# USB.net
KiCad netlist of a schematic drawn in Altium Designer
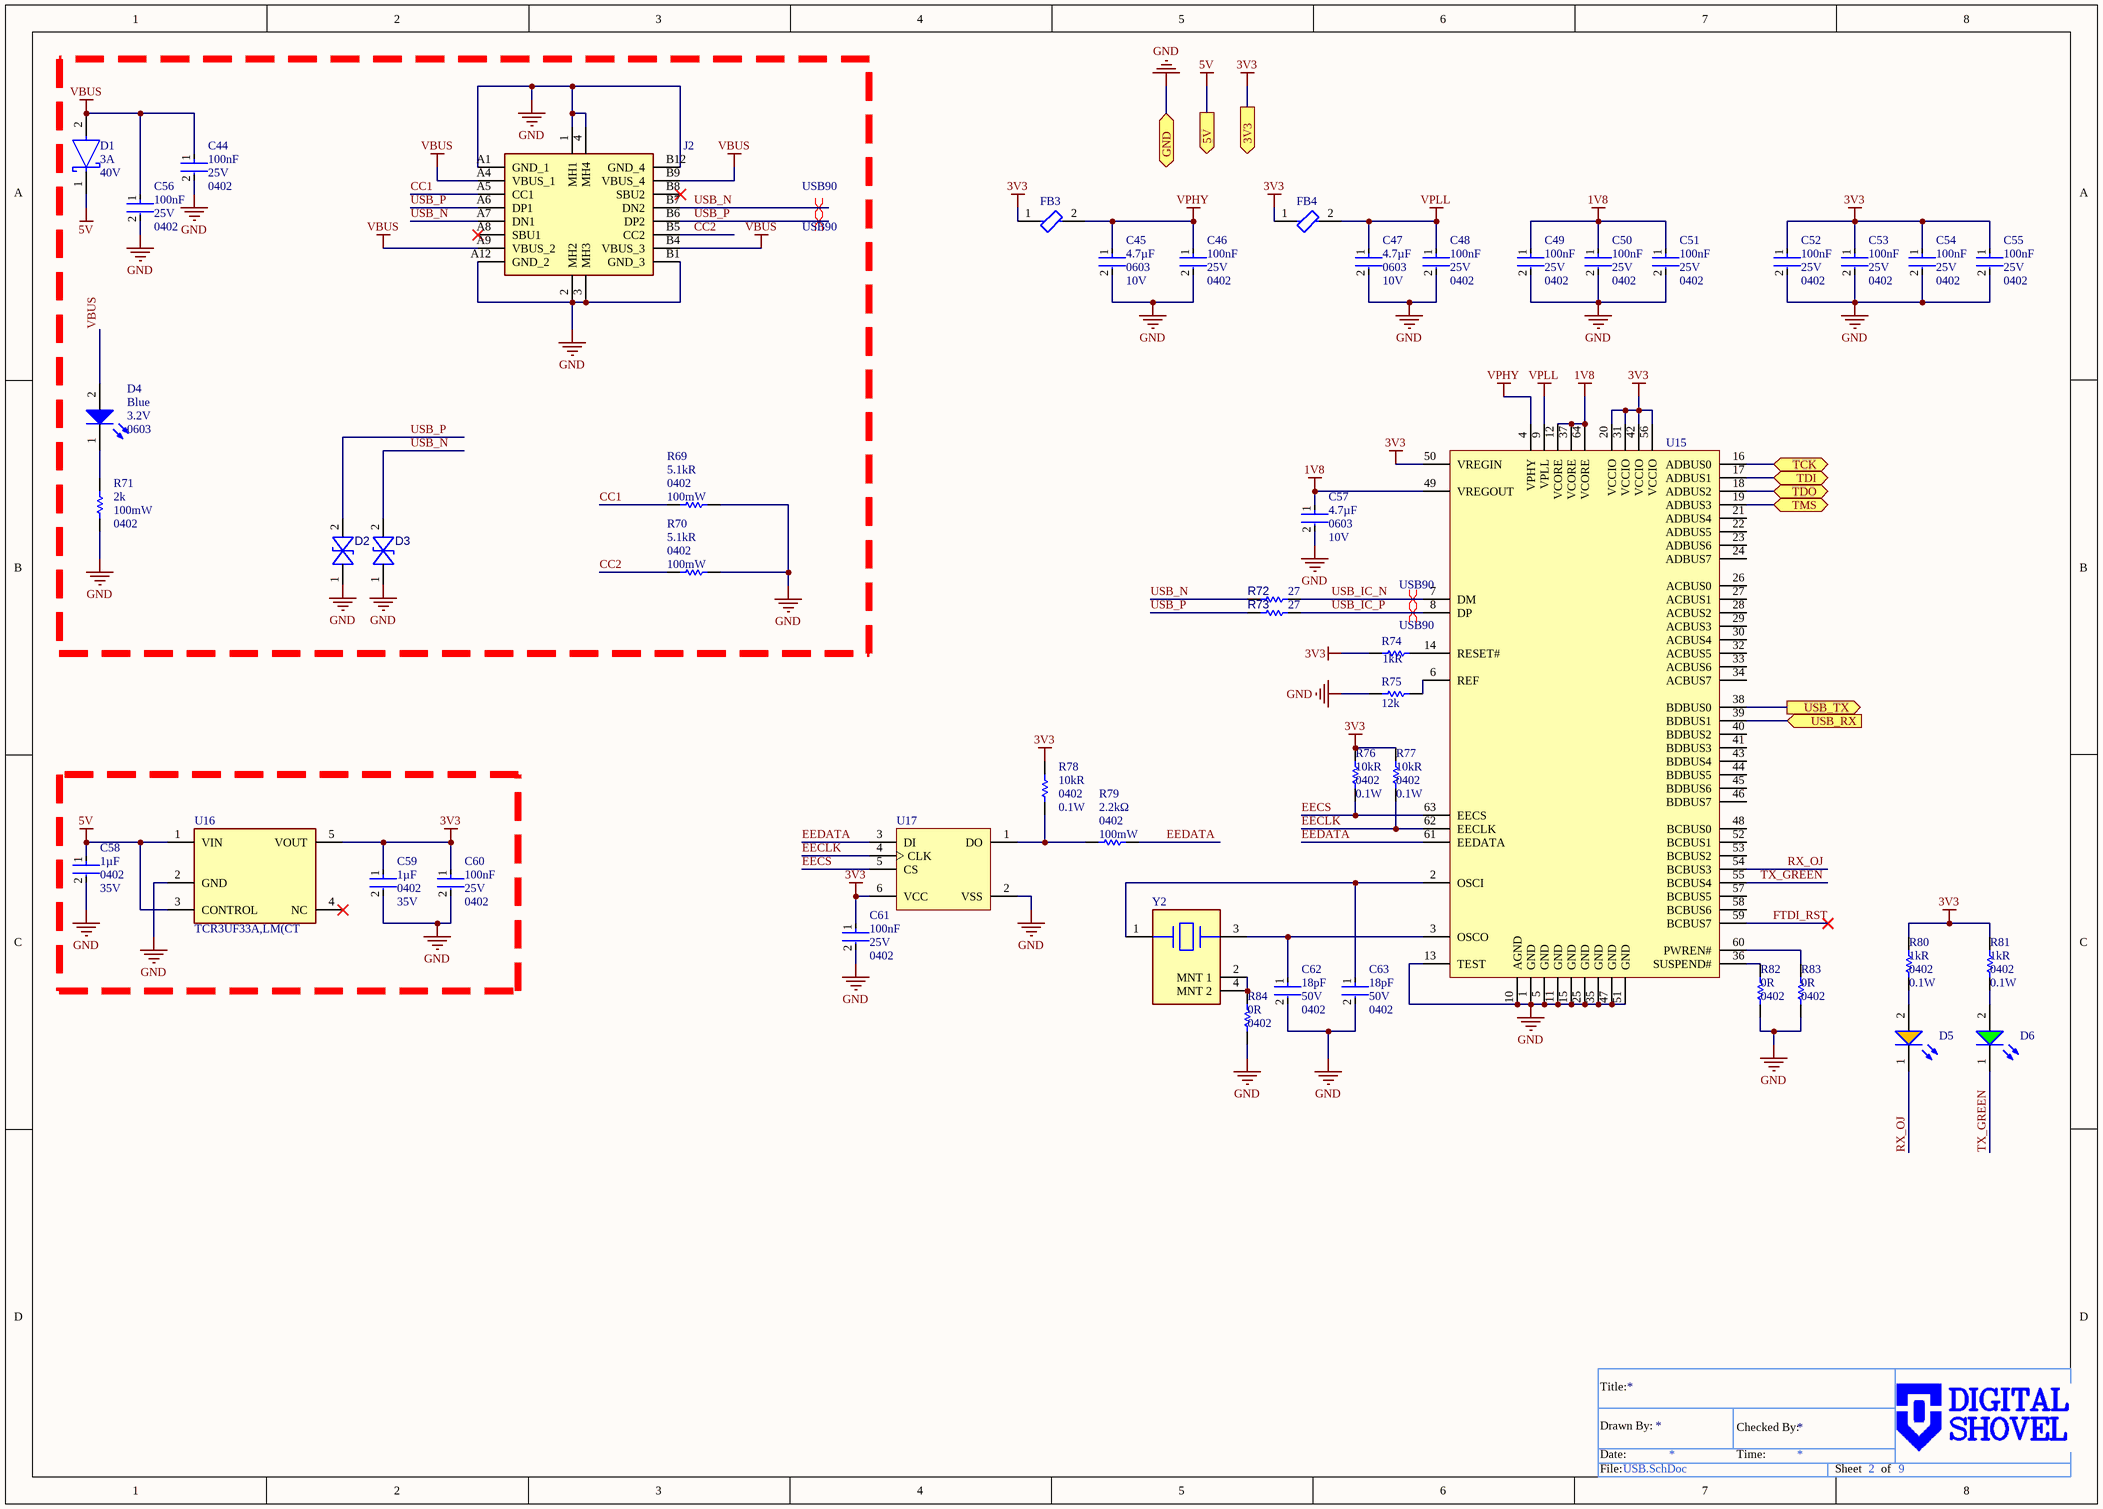
[diagram p0: USB.SchDoc]

(export (version "E")
  (design (tool "Eeschema 10.0.6"))
  (components
    (comp (ref "C44")
      (value "100nF")
      (footprint "FP-CL830-IPC_A")
      (fields
        (field (name "VOLTAGE RATING") "25V")
        (field (name "CASE/PACKAGE") "0402")
        (field (name "Comment") "CL05B104KA5NNNC")
      )
      (libsource (lib "Digital Shovel") (part "b4654b650e69147ec39a6b967a45e02"))
    )
    (comp (ref "C45")
      (value "4.7µF")
      (footprint "FP-CL10-IPC_A")
      (fields
        (field (name "CASE/PACKAGE") "0603")
        (field (name "VOLTAGE RATING") "10V")
        (field (name "Comment") "CL10A475KP8NNNC")
      )
      (libsource (lib "Digital Shovel") (part "b4654b650e69147ec39a6b967a45e02"))
    )
    (comp (ref "C46")
      (value "100nF")
      (footprint "FP-CL830-IPC_A")
      (fields
        (field (name "VOLTAGE RATING") "25V")
        (field (name "CASE/PACKAGE") "0402")
        (field (name "Comment") "CL05B104KA5NNNC")
      )
      (libsource (lib "Digital Shovel") (part "b4654b650e69147ec39a6b967a45e02"))
    )
    (comp (ref "C47")
      (value "4.7µF")
      (footprint "FP-CL10-IPC_A")
      (fields
        (field (name "CASE/PACKAGE") "0603")
        (field (name "VOLTAGE RATING") "10V")
        (field (name "Comment") "CL10A475KP8NNNC")
      )
      (libsource (lib "Digital Shovel") (part "b4654b650e69147ec39a6b967a45e02"))
    )
    (comp (ref "C48")
      (value "100nF")
      (footprint "FP-CL830-IPC_A")
      (fields
        (field (name "VOLTAGE RATING") "25V")
        (field (name "CASE/PACKAGE") "0402")
        (field (name "Comment") "CL05B104KA5NNNC")
      )
      (libsource (lib "Digital Shovel") (part "b4654b650e69147ec39a6b967a45e02"))
    )
    (comp (ref "C49")
      (value "100nF")
      (footprint "FP-CL830-IPC_A")
      (fields
        (field (name "VOLTAGE RATING") "25V")
        (field (name "CASE/PACKAGE") "0402")
        (field (name "Comment") "CL05B104KA5NNNC")
      )
      (libsource (lib "Digital Shovel") (part "b4654b650e69147ec39a6b967a45e02"))
    )
    (comp (ref "C50")
      (value "100nF")
      (footprint "FP-CL830-IPC_A")
      (fields
        (field (name "VOLTAGE RATING") "25V")
        (field (name "CASE/PACKAGE") "0402")
        (field (name "Comment") "CL05B104KA5NNNC")
      )
      (libsource (lib "Digital Shovel") (part "b4654b650e69147ec39a6b967a45e02"))
    )
    (comp (ref "C51")
      (value "100nF")
      (footprint "FP-CL830-IPC_A")
      (fields
        (field (name "VOLTAGE RATING") "25V")
        (field (name "CASE/PACKAGE") "0402")
        (field (name "Comment") "CL05B104KA5NNNC")
      )
      (libsource (lib "Digital Shovel") (part "b4654b650e69147ec39a6b967a45e02"))
    )
    (comp (ref "C52")
      (value "100nF")
      (footprint "FP-CL830-IPC_A")
      (fields
        (field (name "VOLTAGE RATING") "25V")
        (field (name "CASE/PACKAGE") "0402")
        (field (name "Comment") "CL05B104KA5NNNC")
      )
      (libsource (lib "Digital Shovel") (part "b4654b650e69147ec39a6b967a45e02"))
    )
    (comp (ref "C53")
      (value "100nF")
      (footprint "FP-CL830-IPC_A")
      (fields
        (field (name "VOLTAGE RATING") "25V")
        (field (name "CASE/PACKAGE") "0402")
        (field (name "Comment") "CL05B104KA5NNNC")
      )
      (libsource (lib "Digital Shovel") (part "b4654b650e69147ec39a6b967a45e02"))
    )
    (comp (ref "C54")
      (value "100nF")
      (footprint "FP-CL830-IPC_A")
      (fields
        (field (name "VOLTAGE RATING") "25V")
        (field (name "CASE/PACKAGE") "0402")
        (field (name "Comment") "CL05B104KA5NNNC")
      )
      (libsource (lib "Digital Shovel") (part "b4654b650e69147ec39a6b967a45e02"))
    )
    (comp (ref "C55")
      (value "100nF")
      (footprint "FP-CL830-IPC_A")
      (fields
        (field (name "VOLTAGE RATING") "25V")
        (field (name "CASE/PACKAGE") "0402")
        (field (name "Comment") "CL05B104KA5NNNC")
      )
      (libsource (lib "Digital Shovel") (part "b4654b650e69147ec39a6b967a45e02"))
    )
    (comp (ref "C56")
      (value "100nF")
      (footprint "FP-CL830-IPC_A")
      (fields
        (field (name "VOLTAGE RATING") "25V")
        (field (name "CASE/PACKAGE") "0402")
        (field (name "Comment") "CL05B104KA5NNNC")
      )
      (libsource (lib "Digital Shovel") (part "b4654b650e69147ec39a6b967a45e02"))
    )
    (comp (ref "C57")
      (value "4.7µF")
      (footprint "FP-CL10-IPC_A")
      (fields
        (field (name "CASE/PACKAGE") "0603")
        (field (name "VOLTAGE RATING") "10V")
        (field (name "Comment") "CL10A475KP8NNNC")
      )
      (libsource (lib "Digital Shovel") (part "b4654b650e69147ec39a6b967a45e02"))
    )
    (comp (ref "C58")
      (value "1µF")
      (footprint "FP-C1005-050-0_05-IPC_A")
      (fields
        (field (name "CASE/PACKAGE") "0402")
        (field (name "VOLTAGE RATING") "35V")
        (field (name "Comment") "C1005JB1V105K050BC")
      )
      (libsource (lib "Digital Shovel") (part "b4654b650e69147ec39a6b967a45e02"))
    )
    (comp (ref "C59")
      (value "1µF")
      (footprint "FP-C1005-050-0_05-IPC_A")
      (fields
        (field (name "CASE/PACKAGE") "0402")
        (field (name "VOLTAGE RATING") "35V")
        (field (name "Comment") "C1005JB1V105K050BC")
      )
      (libsource (lib "Digital Shovel") (part "b4654b650e69147ec39a6b967a45e02"))
    )
    (comp (ref "C60")
      (value "100nF")
      (footprint "FP-CL830-IPC_A")
      (fields
        (field (name "VOLTAGE RATING") "25V")
        (field (name "CASE/PACKAGE") "0402")
        (field (name "Comment") "CL05B104KA5NNNC")
      )
      (libsource (lib "Digital Shovel") (part "b4654b650e69147ec39a6b967a45e02"))
    )
    (comp (ref "C61")
      (value "100nF")
      (footprint "FP-CL830-IPC_A")
      (fields
        (field (name "VOLTAGE RATING") "25V")
        (field (name "CASE/PACKAGE") "0402")
        (field (name "Comment") "CL05B104KA5NNNC")
      )
      (libsource (lib "Digital Shovel") (part "b4654b650e69147ec39a6b967a45e02"))
    )
    (comp (ref "C62")
      (value "18pF")
      (footprint "FP-GJM155-0_05-IPC_A")
      (fields
        (field (name "CASE/PACKAGE") "0402")
        (field (name "VOLTAGE RATING") "50V")
        (field (name "Comment") "GJM1555C1H180GB01D")
      )
      (libsource (lib "Digital Shovel") (part "02cd4be3c70576c341d710602a673aa"))
    )
    (comp (ref "C63")
      (value "18pF")
      (footprint "FP-GJM155-0_05-IPC_A")
      (fields
        (field (name "CASE/PACKAGE") "0402")
        (field (name "VOLTAGE RATING") "50V")
        (field (name "Comment") "GJM1555C1H180GB01D")
      )
      (libsource (lib "Digital Shovel") (part "02cd4be3c70576c341d710602a673aa"))
    )
    (comp (ref "D1")
      (value "3A")
      (footprint "FP-SOD123W-MFG")
      (description "Rectifier Diode, Schottky, 1 Phase, 1 Element, 3A, 40V V(RRM), Silicon")
      (fields
        (field (name "MANUFACTURER") "Nexperia")
        (field (name "VOLTAGE RATING") "40V")
        (field (name "Comment") "PMEG3020ER,115")
      )
      (libsource (lib "Digital Shovel") (part "e9b750318ede8d9850c058872da20e7"))
    )
    (comp (ref "D2")
      (value "TPD1E01B04DPYR")
      (footprint "TPD1E01B04DPYR-Footprint-1")
      (description "Trans Voltage Suppressor Diode, 27W, 3.6V V(RWM), Bidirectional, 1 Element, Silicon")
      (libsource (lib "Digital Shovel") (part "TPD1E01B04DPYR"))
    )
    (comp (ref "D3")
      (value "TPD1E01B04DPYR")
      (footprint "TPD1E01B04DPYR-Footprint-1")
      (description "Trans Voltage Suppressor Diode, 27W, 3.6V V(RWM), Bidirectional, 1 Element, Silicon")
      (libsource (lib "Digital Shovel") (part "TPD1E01B04DPYR"))
    )
    (comp (ref "D4")
      (value "150060BS75000")
      (footprint "WL-SMCW_0603_150060xx75000")
      (description "Single Color LED, Blue, Water Clear, 1.1mm")
      (fields
        (field (name "FORWARD VOLTAGE") "3.2V")
        (field (name "CASE/PACKAGE") "0603")
        (field (name "COLOUR") "Blue")
      )
      (libsource (lib "Digital Shovel") (part "LED_Blue_2A-1K"))
    )
    (comp (ref "D5")
      (value "150060AS75000")
      (footprint "WL-SMCW_0603_150060xx75000")
      (description "Single Color LED, Amber, Water Clear, 1.1mm")
      (libsource (lib "Digital Shovel") (part "LED_Amber_2A-1K"))
    )
    (comp (ref "D6")
      (value "150060VS75000")
      (footprint "WL-SMCW_0603_150060xx75000")
      (description "Single Color LED, Bright Green, Water Clear, 1.1mm")
      (libsource (lib "Digital Shovel") (part "LED_Green_2A-1K"))
    )
    (comp (ref "FB3")
      (value "BLM21PG300SN1D")
      (footprint "FP-BLM21-0_2-t0_85-e0_5-d-MFG")
      (description "Chip Ferrite Bead, 0805, 30Ω @ 100MHz, 0.014Ω, , 4A")
      (fields (field (name "TOLERANCE") "25%"))
      (libsource (lib "Altium Content Vault") (part "5f30dd21d616792df468990f7003faa"))
    )
    (comp (ref "FB4")
      (value "BLM21PG300SN1D")
      (footprint "FP-BLM21-0_2-t0_85-e0_5-d-MFG")
      (description "Chip Ferrite Bead, 0805, 30Ω @ 100MHz, 0.014Ω, , 4A")
      (fields (field (name "TOLERANCE") "25%"))
      (libsource (lib "Altium Content Vault") (part "5f30dd21d616792df468990f7003faa"))
    )
    (comp (ref "J2")
      (value "USB4145-03-0170-C")
      (footprint "GCT_USB4145-03-0170-C_REVA2")
      (description "USB Connectors USB-C Rec 3u Vert 16P SMT 1.7mm TH stakes H7.46mm T+R+Cap")
      (fields (field (name "MP") "USB4145-03-0170-C_REVA2"))
      (libsource (lib "Digital Shovel") (part "USB4145-03-0170-C"))
    )
    (comp (ref "R69")
      (value "5.1kR")
      (footprint "RESC1005X40X25LL10T10")
      (fields
        (field (name "PACKAGE") "0402")
        (field (name "MANUFACTURER") "KOA Speer")
        (field (name "POWER") "100mW")
        (field (name "Comment") "RK73H1ETTP5101F")
      )
      (libsource (lib "Digital Shovel") (part "RES"))
    )
    (comp (ref "R70")
      (value "5.1kR")
      (footprint "RESC1005X40X25LL10T10")
      (fields
        (field (name "PACKAGE") "0402")
        (field (name "MANUFACTURER") "KOA Speer")
        (field (name "POWER") "100mW")
        (field (name "Comment") "RK73H1ETTP5101F")
      )
      (libsource (lib "Digital Shovel") (part "RES"))
    )
    (comp (ref "R71")
      (value "2k")
      (footprint "RESC1005X40X25LL10T10")
      (fields
        (field (name "CASE/PACKAGE") "0402")
        (field (name "TOLERANCE") "1%")
        (field (name "POWER") "100mW")
        (field (name "Comment") "RK73H1ETTP2001F")
      )
      (libsource (lib "Digital Shovel") (part "RES"))
    )
    (comp (ref "R72")
      (value "27")
      (footprint "RK73H1ETTP27R0F-Footprint-1")
      (fields
        (field (name "TOLERANCE") "1%")
        (field (name "POWER") "100mW")
        (field (name "Comment") "RK73H1ETTP27R0F")
      )
      (libsource (lib "Digital Shovel") (part "RN73R2ATTD2003B25"))
    )
    (comp (ref "R73")
      (value "27")
      (footprint "RK73H1ETTP27R0F-Footprint-1")
      (fields
        (field (name "TOLERANCE") "1%")
        (field (name "POWER") "100mW")
        (field (name "Comment") "RK73H1ETTP27R0F")
      )
      (libsource (lib "Digital Shovel") (part "RN73R2ATTD2003B25"))
    )
    (comp (ref "R74")
      (value "1kR")
      (footprint "RESC1005X40X25LL10T10")
      (fields (field (name "MANUFACTURER") "KOA Speer") (field (name "Comment") "RK73H1ETTP1001F"))
      (libsource (lib "Digital Shovel") (part "RES"))
    )
    (comp (ref "R75")
      (value "12k")
      (footprint "RESC1005X40X25LL10T10")
      (fields
        (field (name "TOLERANCE") "1%")
        (field (name "POWER") "100mW")
        (field (name "Comment") "RK73H1ETTP1202F")
      )
      (libsource (lib "Digital Shovel") (part "RES"))
    )
    (comp (ref "R76")
      (value "10kR")
      (footprint "RESC1005X40X25LL10T10")
      (fields
        (field (name "PACKAGE") "0402")
        (field (name "POWER") "0.1W")
        (field (name "Comment") "RK73H1ETTP1002F")
      )
      (libsource (lib "Digital Shovel") (part "RES"))
    )
    (comp (ref "R77")
      (value "10kR")
      (footprint "RESC1005X40X25LL10T10")
      (fields
        (field (name "PACKAGE") "0402")
        (field (name "POWER") "0.1W")
        (field (name "Comment") "RK73H1ETTP1002F")
      )
      (libsource (lib "Digital Shovel") (part "RES"))
    )
    (comp (ref "R78")
      (value "10kR")
      (footprint "RESC1005X40X25LL10T10")
      (fields
        (field (name "PACKAGE") "0402")
        (field (name "POWER RATING") "0.1W")
        (field (name "Comment") "RK73H1ETTP1002F")
      )
      (libsource (lib "Digital Shovel") (part "RES"))
    )
    (comp (ref "R79")
      (value "2.2kΩ")
      (footprint "RK73H1ETTP2201F-Footprint-1")
      (fields
        (field (name "PACKAGE") "0402")
        (field (name "RATING") "100mW")
        (field (name "MANUFACTURER") "KOA Speer")
        (field (name "Comment") "RK73H1ETTP2201F")
      )
      (libsource (lib "Digital Shovel") (part "RES"))
    )
    (comp (ref "R80")
      (value "1kR")
      (footprint "RESC1005X40X25LL10T10")
      (fields
        (field (name "MANUFACTURER") "KOA Speer")
        (field (name "PACKAGE") "0402")
        (field (name "POWER") "0.1W")
        (field (name "Comment") "RK73H1ETTP1001F")
      )
      (libsource (lib "Digital Shovel") (part "RES"))
    )
    (comp (ref "R81")
      (value "1kR")
      (footprint "RESC1005X40X25LL10T10")
      (fields
        (field (name "MANUFACTURER") "KOA Speer")
        (field (name "PACKAGE") "0402")
        (field (name "POWER") "0.1W")
        (field (name "Comment") "RK73H1ETTP1001F")
      )
      (libsource (lib "Digital Shovel") (part "RES"))
    )
    (comp (ref "R82")
      (value "0R")
      (footprint "FP-RK73Z1E-IPC_B")
      (description "Metal Glaze/thick Film, 0ohm, Surface Mount, 0402")
      (fields (field (name "PACKAGE") "0402") (field (name "Comment") "RK73Z1ETTP"))
      (libsource (lib "Digital Shovel") (part "1029c3af85768c4190bb7ad29bc67b5"))
    )
    (comp (ref "R83")
      (value "0R")
      (footprint "FP-RK73Z1E-IPC_B")
      (description "Metal Glaze/thick Film, 0ohm, Surface Mount, 0402")
      (fields (field (name "PACKAGE") "0402") (field (name "Comment") "RK73Z1ETTP"))
      (libsource (lib "Digital Shovel") (part "1029c3af85768c4190bb7ad29bc67b5"))
    )
    (comp (ref "R84")
      (value "0R")
      (footprint "FP-RK73Z1E-IPC_B")
      (description "Metal Glaze/thick Film, 0ohm, Surface Mount, 0402")
      (fields (field (name "PACKAGE") "0402") (field (name "Comment") "RK73Z1ETTP"))
      (libsource (lib "Digital Shovel") (part "1029c3af85768c4190bb7ad29bc67b5"))
    )
    (comp (ref "U15")
      (value "FT2232HL-REEL")
      (footprint "LQFP-64_M")
      (description "USB Bus Controller, CMOS, PQFP64")
      (fields (field (name "MANUFACTURER") "FTDI"))
      (libsource (lib "Digital Shovel") (part "COM-UART-FT2232H-LQFP64"))
    )
    (comp (ref "U16")
      (value "TCR3UF33A,LM(CT")
      (footprint "TCR3UF33A,LM(CT-Footprint-1")
      (description "(ldo) Linear Voltage Reg, Vin: 6")
      (fields (field (name "MANUFACTURER") "Toshiba"))
      (libsource (lib "Digital Shovel") (part "TCR3UF33A,LM(CT-Symbol-1"))
    )
    (comp (ref "U17")
      (value "93LC46BT-I/OT")
      (footprint "SOT-23-OT6_M")
      (description "EEPROM, 64X16, Serial, CMOS, PDSO6")
      (fields (field (name "MANUFACTURER") "Microchip Technology"))
      (libsource (lib "Digital Shovel") (part "MEM-SEEPROM-93AA46B-OT-6"))
    )
    (comp (ref "Y2")
      (value "ABM10-166-12.000MHZ-T3")
      (footprint "FP-ABM10-166-167-MFG")
      (description "Crystal 12MHz ±10ppm (Tol) ±10ppm (Stability) 8pF FUND 125Ohm 4-Pin SMD T/R")
      (fields (field (name "MANUFACTURER") "TI"))
      (libsource (lib "Digital Shovel") (part "c1e6c4da84e2560fa339d1e93faccc5"))
    )
  )
  (nets
    (net (code "1") (name "/CC1") (class "Default")
      (node (ref "J2") (pin "A5") (pinfunction "CC1_A5") (pintype "passive"))
      (node (ref "R69") (pin "1") (pinfunction "1_1") (pintype "passive"))
    )
    (net (code "2") (name "/CC2") (class "Default")
      (node (ref "J2") (pin "B5") (pinfunction "CC2_B5") (pintype "passive"))
      (node (ref "R70") (pin "1") (pinfunction "1_1") (pintype "passive"))
    )
    (net (code "3") (name "/EECLK") (class "Default")
      (node (ref "R77") (pin "1") (pinfunction "1_1") (pintype "passive"))
      (node (ref "U15") (pin "62") (pinfunction "EECLK_62") (pintype "passive"))
      (node (ref "U17") (pin "4") (pinfunction "CLK_4") (pintype "passive"))
    )
    (net (code "4") (name "/EECS") (class "Default")
      (node (ref "R76") (pin "1") (pinfunction "1_1") (pintype "passive"))
      (node (ref "U15") (pin "63") (pinfunction "EECS_63") (pintype "passive"))
      (node (ref "U17") (pin "5") (pinfunction "CS_5") (pintype "passive"))
    )
    (net (code "5") (name "/EEDATA") (class "Default")
      (node (ref "R79") (pin "2") (pinfunction "2_2") (pintype "passive"))
      (node (ref "U15") (pin "61") (pinfunction "EEDATA_61") (pintype "passive"))
      (node (ref "U17") (pin "3") (pinfunction "DI_3") (pintype "passive"))
    )
    (net (code "6") (name "/FTDI_RST") (class "Default")
      (node (ref "U15") (pin "59") (pinfunction "BCBUS7_59") (pintype "passive+no_connect"))
    )
    (net (code "7") (name "/RX_OJ") (class "Default")
      (node (ref "D5") (pin "1") (pinfunction "K_1") (pintype "passive"))
      (node (ref "U15") (pin "54") (pinfunction "BCBUS3_54") (pintype "passive"))
    )
    (net (code "8") (name "/TCK") (class "Default")
      (node (ref "U15") (pin "16") (pinfunction "ADBUS0_16") (pintype "passive"))
    )
    (net (code "9") (name "/TDI") (class "Default")
      (node (ref "U15") (pin "17") (pinfunction "ADBUS1_17") (pintype "passive"))
    )
    (net (code "10") (name "/TDO") (class "Default")
      (node (ref "U15") (pin "18") (pinfunction "ADBUS2_18") (pintype "passive"))
    )
    (net (code "11") (name "/TMS") (class "Default")
      (node (ref "U15") (pin "19") (pinfunction "ADBUS3_19") (pintype "passive"))
    )
    (net (code "12") (name "/TX_GREEN") (class "Default")
      (node (ref "D6") (pin "1") (pinfunction "K_1") (pintype "passive"))
      (node (ref "U15") (pin "55") (pinfunction "BCBUS4_55") (pintype "passive"))
    )
    (net (code "13") (name "/USB_IC_N") (class "Default")
      (node (ref "R72") (pin "2") (pinfunction "2_2") (pintype "passive"))
      (node (ref "U15") (pin "7") (pinfunction "DM_7") (pintype "passive"))
    )
    (net (code "14") (name "/USB_IC_P") (class "Default")
      (node (ref "R73") (pin "2") (pinfunction "2_2") (pintype "passive"))
      (node (ref "U15") (pin "8") (pinfunction "DP_8") (pintype "passive"))
    )
    (net (code "15") (name "/USB_N") (class "Default")
      (node (ref "D3") (pin "2") (pinfunction "2_2") (pintype "passive"))
      (node (ref "J2") (pin "A7") (pinfunction "DN1_A7") (pintype "passive"))
      (node (ref "J2") (pin "B7") (pinfunction "DN2_B7") (pintype "passive"))
      (node (ref "R72") (pin "1") (pinfunction "1_1") (pintype "passive"))
    )
    (net (code "16") (name "/USB_P") (class "Default")
      (node (ref "D2") (pin "2") (pinfunction "2_2") (pintype "passive"))
      (node (ref "J2") (pin "A6") (pinfunction "DP1_A6") (pintype "passive"))
      (node (ref "J2") (pin "B6") (pinfunction "DP2_B6") (pintype "passive"))
      (node (ref "R73") (pin "1") (pinfunction "1_1") (pintype "passive"))
    )
    (net (code "17") (name "/USB_RX") (class "Default")
      (node (ref "U15") (pin "39") (pinfunction "BDBUS1_39") (pintype "passive"))
    )
    (net (code "18") (name "/USB_TX") (class "Default")
      (node (ref "U15") (pin "38") (pinfunction "BDBUS0_38") (pintype "passive"))
    )
    (net (code "19") (name "1V8") (class "Default")
      (node (ref "C49") (pin "1") (pinfunction "1_1") (pintype "passive"))
      (node (ref "C50") (pin "1") (pinfunction "1_1") (pintype "passive"))
      (node (ref "C51") (pin "1") (pinfunction "1_1") (pintype "passive"))
      (node (ref "C57") (pin "1") (pinfunction "1_1") (pintype "passive"))
      (node (ref "U15") (pin "12") (pinfunction "VCORE_12") (pintype "passive"))
      (node (ref "U15") (pin "37") (pinfunction "VCORE_37") (pintype "passive"))
      (node (ref "U15") (pin "49") (pinfunction "VREGOUT_49") (pintype "passive"))
      (node (ref "U15") (pin "64") (pinfunction "VCORE_64") (pintype "passive"))
    )
    (net (code "20") (name "3V3") (class "Default")
      (node (ref "C52") (pin "1") (pinfunction "1_1") (pintype "passive"))
      (node (ref "C53") (pin "1") (pinfunction "1_1") (pintype "passive"))
      (node (ref "C54") (pin "1") (pinfunction "1_1") (pintype "passive"))
      (node (ref "C55") (pin "1") (pinfunction "1_1") (pintype "passive"))
      (node (ref "C59") (pin "1") (pinfunction "1_1") (pintype "passive"))
      (node (ref "C60") (pin "1") (pinfunction "1_1") (pintype "passive"))
      (node (ref "C61") (pin "1") (pinfunction "1_1") (pintype "passive"))
      (node (ref "FB3") (pin "1") (pinfunction "1_1") (pintype "passive"))
      (node (ref "FB4") (pin "1") (pinfunction "1_1") (pintype "passive"))
      (node (ref "R74") (pin "1") (pinfunction "1_1") (pintype "passive"))
      (node (ref "R76") (pin "2") (pinfunction "2_2") (pintype "passive"))
      (node (ref "R77") (pin "2") (pinfunction "2_2") (pintype "passive"))
      (node (ref "R78") (pin "2") (pinfunction "2_2") (pintype "passive"))
      (node (ref "R80") (pin "2") (pinfunction "2_2") (pintype "passive"))
      (node (ref "R81") (pin "2") (pinfunction "2_2") (pintype "passive"))
      (node (ref "U15") (pin "20") (pinfunction "VCCIO_20") (pintype "passive"))
      (node (ref "U15") (pin "31") (pinfunction "VCCIO_31") (pintype "passive"))
      (node (ref "U15") (pin "42") (pinfunction "VCCIO_42") (pintype "passive"))
      (node (ref "U15") (pin "50") (pinfunction "VREGIN_50") (pintype "passive"))
      (node (ref "U15") (pin "56") (pinfunction "VCCIO_56") (pintype "passive"))
      (node (ref "U16") (pin "5") (pinfunction "VOUT_5") (pintype "passive"))
      (node (ref "U17") (pin "6") (pinfunction "VCC_6") (pintype "passive"))
    )
    (net (code "21") (name "5V") (class "Default")
      (node (ref "C58") (pin "1") (pinfunction "1_1") (pintype "passive"))
      (node (ref "D1") (pin "1") (pinfunction "C_1") (pintype "passive"))
      (node (ref "U16") (pin "1") (pinfunction "VIN_1") (pintype "passive"))
      (node (ref "U16") (pin "3") (pinfunction "CONTROL_3") (pintype "passive"))
    )
    (net (code "22") (name "GND") (class "Default")
      (node (ref "C44") (pin "2") (pinfunction "2_2") (pintype "passive"))
      (node (ref "C45") (pin "2") (pinfunction "2_2") (pintype "passive"))
      (node (ref "C46") (pin "2") (pinfunction "2_2") (pintype "passive"))
      (node (ref "C47") (pin "2") (pinfunction "2_2") (pintype "passive"))
      (node (ref "C48") (pin "2") (pinfunction "2_2") (pintype "passive"))
      (node (ref "C49") (pin "2") (pinfunction "2_2") (pintype "passive"))
      (node (ref "C50") (pin "2") (pinfunction "2_2") (pintype "passive"))
      (node (ref "C51") (pin "2") (pinfunction "2_2") (pintype "passive"))
      (node (ref "C52") (pin "2") (pinfunction "2_2") (pintype "passive"))
      (node (ref "C53") (pin "2") (pinfunction "2_2") (pintype "passive"))
      (node (ref "C54") (pin "2") (pinfunction "2_2") (pintype "passive"))
      (node (ref "C55") (pin "2") (pinfunction "2_2") (pintype "passive"))
      (node (ref "C56") (pin "2") (pinfunction "2_2") (pintype "passive"))
      (node (ref "C57") (pin "2") (pinfunction "2_2") (pintype "passive"))
      (node (ref "C58") (pin "2") (pinfunction "2_2") (pintype "passive"))
      (node (ref "C59") (pin "2") (pinfunction "2_2") (pintype "passive"))
      (node (ref "C60") (pin "2") (pinfunction "2_2") (pintype "passive"))
      (node (ref "C61") (pin "2") (pinfunction "2_2") (pintype "passive"))
      (node (ref "C62") (pin "2") (pinfunction "2_2") (pintype "passive"))
      (node (ref "C63") (pin "2") (pinfunction "2_2") (pintype "passive"))
      (node (ref "D2") (pin "1") (pinfunction "1_1") (pintype "passive"))
      (node (ref "D3") (pin "1") (pinfunction "1_1") (pintype "passive"))
      (node (ref "J2") (pin "1") (pinfunction "MH1_1") (pintype "passive"))
      (node (ref "J2") (pin "2") (pinfunction "MH2_2") (pintype "passive"))
      (node (ref "J2") (pin "3") (pinfunction "MH3_3") (pintype "passive"))
      (node (ref "J2") (pin "4") (pinfunction "MH4_4") (pintype "passive"))
      (node (ref "J2") (pin "A1") (pinfunction "GND_1_A1") (pintype "passive"))
      (node (ref "J2") (pin "A12") (pinfunction "GND_2_A12") (pintype "passive"))
      (node (ref "J2") (pin "B1") (pinfunction "GND_3_B1") (pintype "passive"))
      (node (ref "J2") (pin "B12") (pinfunction "GND_4_B12") (pintype "passive"))
      (node (ref "R69") (pin "2") (pinfunction "2_2") (pintype "passive"))
      (node (ref "R70") (pin "2") (pinfunction "2_2") (pintype "passive"))
      (node (ref "R71") (pin "1") (pinfunction "1_1") (pintype "passive"))
      (node (ref "R75") (pin "1") (pinfunction "1_1") (pintype "passive"))
      (node (ref "R82") (pin "1") (pinfunction "1_1") (pintype "passive"))
      (node (ref "R83") (pin "1") (pinfunction "1_1") (pintype "passive"))
      (node (ref "R84") (pin "1") (pinfunction "1_1") (pintype "passive"))
      (node (ref "U15") (pin "1") (pinfunction "GND_1") (pintype "passive"))
      (node (ref "U15") (pin "10") (pinfunction "AGND_10") (pintype "passive"))
      (node (ref "U15") (pin "11") (pinfunction "GND_11") (pintype "passive"))
      (node (ref "U15") (pin "13") (pinfunction "TEST_13") (pintype "passive"))
      (node (ref "U15") (pin "15") (pinfunction "GND_15") (pintype "passive"))
      (node (ref "U15") (pin "25") (pinfunction "GND_25") (pintype "passive"))
      (node (ref "U15") (pin "35") (pinfunction "GND_35") (pintype "passive"))
      (node (ref "U15") (pin "47") (pinfunction "GND_47") (pintype "passive"))
      (node (ref "U15") (pin "5") (pinfunction "GND_5") (pintype "passive"))
      (node (ref "U15") (pin "51") (pinfunction "GND_51") (pintype "passive"))
      (node (ref "U16") (pin "2") (pinfunction "GND_2") (pintype "passive"))
      (node (ref "U17") (pin "2") (pinfunction "VSS_2") (pintype "passive"))
    )
    (net (code "23") (name "Net-(D4-K)") (class "Default")
      (node (ref "D4") (pin "1") (pinfunction "K_1") (pintype "passive"))
      (node (ref "R71") (pin "2") (pinfunction "2_2") (pintype "passive"))
    )
    (net (code "24") (name "Net-(D5-A)") (class "Default")
      (node (ref "D5") (pin "2") (pinfunction "A_2") (pintype "passive"))
      (node (ref "R80") (pin "1") (pinfunction "1_1") (pintype "passive"))
    )
    (net (code "25") (name "Net-(D6-A)") (class "Default")
      (node (ref "D6") (pin "2") (pinfunction "A_2") (pintype "passive"))
      (node (ref "R81") (pin "1") (pinfunction "1_1") (pintype "passive"))
    )
    (net (code "26") (name "Net-(U15-OSCI)") (class "Default")
      (node (ref "C63") (pin "1") (pinfunction "1_1") (pintype "passive"))
      (node (ref "U15") (pin "2") (pinfunction "OSCI_2") (pintype "passive"))
      (node (ref "Y2") (pin "1") (pinfunction "1_1") (pintype "passive"))
    )
    (net (code "27") (name "Net-(U15-OSCO)") (class "Default")
      (node (ref "C62") (pin "1") (pinfunction "1_1") (pintype "passive"))
      (node (ref "U15") (pin "3") (pinfunction "OSCO_3") (pintype "passive"))
      (node (ref "Y2") (pin "3") (pinfunction "3_3") (pintype "passive"))
    )
    (net (code "28") (name "Net-(U15-PWREN#)") (class "Default")
      (node (ref "R83") (pin "2") (pinfunction "2_2") (pintype "passive"))
      (node (ref "U15") (pin "60") (pinfunction "PWREN#_60") (pintype "passive"))
    )
    (net (code "29") (name "Net-(U15-REF)") (class "Default")
      (node (ref "R75") (pin "2") (pinfunction "2_2") (pintype "passive"))
      (node (ref "U15") (pin "6") (pinfunction "REF_6") (pintype "passive"))
    )
    (net (code "30") (name "Net-(U15-RESET#)") (class "Default")
      (node (ref "R74") (pin "2") (pinfunction "2_2") (pintype "passive"))
      (node (ref "U15") (pin "14") (pinfunction "RESET#_14") (pintype "passive"))
    )
    (net (code "31") (name "Net-(U15-SUSPEND#)") (class "Default")
      (node (ref "R82") (pin "2") (pinfunction "2_2") (pintype "passive"))
      (node (ref "U15") (pin "36") (pinfunction "SUSPEND#_36") (pintype "passive"))
    )
    (net (code "32") (name "Net-(U17-DO)") (class "Default")
      (node (ref "R78") (pin "1") (pinfunction "1_1") (pintype "passive"))
      (node (ref "R79") (pin "1") (pinfunction "1_1") (pintype "passive"))
      (node (ref "U17") (pin "1") (pinfunction "DO_1") (pintype "passive"))
    )
    (net (code "33") (name "Net-(Y2-MNT_1)") (class "Default")
      (node (ref "R84") (pin "2") (pinfunction "2_2") (pintype "passive"))
      (node (ref "Y2") (pin "2") (pinfunction "MNT_1_2") (pintype "passive"))
      (node (ref "Y2") (pin "4") (pinfunction "MNT_2_4") (pintype "passive"))
    )
    (net (code "34") (name "VBUS") (class "Default")
      (node (ref "C44") (pin "1") (pinfunction "1_1") (pintype "passive"))
      (node (ref "C56") (pin "1") (pinfunction "1_1") (pintype "passive"))
      (node (ref "D1") (pin "2") (pinfunction "A_2") (pintype "passive"))
      (node (ref "D4") (pin "2") (pinfunction "A_2") (pintype "passive"))
      (node (ref "J2") (pin "A4") (pinfunction "VBUS_1_A4") (pintype "passive"))
      (node (ref "J2") (pin "A9") (pinfunction "VBUS_2_A9") (pintype "passive"))
      (node (ref "J2") (pin "B4") (pinfunction "VBUS_3_B4") (pintype "passive"))
      (node (ref "J2") (pin "B9") (pinfunction "VBUS_4_B9") (pintype "passive"))
    )
    (net (code "35") (name "VPHY") (class "Default")
      (node (ref "C45") (pin "1") (pinfunction "1_1") (pintype "passive"))
      (node (ref "C46") (pin "1") (pinfunction "1_1") (pintype "passive"))
      (node (ref "FB3") (pin "2") (pinfunction "2_2") (pintype "passive"))
      (node (ref "U15") (pin "4") (pinfunction "VPHY_4") (pintype "passive"))
    )
    (net (code "36") (name "VPLL") (class "Default")
      (node (ref "C47") (pin "1") (pinfunction "1_1") (pintype "passive"))
      (node (ref "C48") (pin "1") (pinfunction "1_1") (pintype "passive"))
      (node (ref "FB4") (pin "2") (pinfunction "2_2") (pintype "passive"))
      (node (ref "U15") (pin "9") (pinfunction "VPLL_9") (pintype "passive"))
    )
    (net (code "37") (name "unconnected-(J2-SBU1-PadA8)") (class "Default")
      (node (ref "J2") (pin "A8") (pinfunction "SBU1_A8") (pintype "passive+no_connect"))
    )
    (net (code "38") (name "unconnected-(J2-SBU2-PadB8)") (class "Default")
      (node (ref "J2") (pin "B8") (pinfunction "SBU2_B8") (pintype "passive+no_connect"))
    )
    (net (code "39") (name "unconnected-(U15-ACBUS0-Pad26)") (class "Default")
      (node (ref "U15") (pin "26") (pinfunction "ACBUS0_26") (pintype "passive"))
    )
    (net (code "40") (name "unconnected-(U15-ACBUS1-Pad27)") (class "Default")
      (node (ref "U15") (pin "27") (pinfunction "ACBUS1_27") (pintype "passive"))
    )
    (net (code "41") (name "unconnected-(U15-ACBUS2-Pad28)") (class "Default")
      (node (ref "U15") (pin "28") (pinfunction "ACBUS2_28") (pintype "passive"))
    )
    (net (code "42") (name "unconnected-(U15-ACBUS3-Pad29)") (class "Default")
      (node (ref "U15") (pin "29") (pinfunction "ACBUS3_29") (pintype "passive"))
    )
    (net (code "43") (name "unconnected-(U15-ACBUS4-Pad30)") (class "Default")
      (node (ref "U15") (pin "30") (pinfunction "ACBUS4_30") (pintype "passive"))
    )
    (net (code "44") (name "unconnected-(U15-ACBUS5-Pad32)") (class "Default")
      (node (ref "U15") (pin "32") (pinfunction "ACBUS5_32") (pintype "passive"))
    )
    (net (code "45") (name "unconnected-(U15-ACBUS6-Pad33)") (class "Default")
      (node (ref "U15") (pin "33") (pinfunction "ACBUS6_33") (pintype "passive"))
    )
    (net (code "46") (name "unconnected-(U15-ACBUS7-Pad34)") (class "Default")
      (node (ref "U15") (pin "34") (pinfunction "ACBUS7_34") (pintype "passive"))
    )
    (net (code "47") (name "unconnected-(U15-ADBUS4-Pad21)") (class "Default")
      (node (ref "U15") (pin "21") (pinfunction "ADBUS4_21") (pintype "passive"))
    )
    (net (code "48") (name "unconnected-(U15-ADBUS5-Pad22)") (class "Default")
      (node (ref "U15") (pin "22") (pinfunction "ADBUS5_22") (pintype "passive"))
    )
    (net (code "49") (name "unconnected-(U15-ADBUS6-Pad23)") (class "Default")
      (node (ref "U15") (pin "23") (pinfunction "ADBUS6_23") (pintype "passive"))
    )
    (net (code "50") (name "unconnected-(U15-ADBUS7-Pad24)") (class "Default")
      (node (ref "U15") (pin "24") (pinfunction "ADBUS7_24") (pintype "passive"))
    )
    (net (code "51") (name "unconnected-(U15-BCBUS0-Pad48)") (class "Default")
      (node (ref "U15") (pin "48") (pinfunction "BCBUS0_48") (pintype "passive"))
    )
    (net (code "52") (name "unconnected-(U15-BCBUS1-Pad52)") (class "Default")
      (node (ref "U15") (pin "52") (pinfunction "BCBUS1_52") (pintype "passive"))
    )
    (net (code "53") (name "unconnected-(U15-BCBUS2-Pad53)") (class "Default")
      (node (ref "U15") (pin "53") (pinfunction "BCBUS2_53") (pintype "passive"))
    )
    (net (code "54") (name "unconnected-(U15-BCBUS5-Pad57)") (class "Default")
      (node (ref "U15") (pin "57") (pinfunction "BCBUS5_57") (pintype "passive"))
    )
    (net (code "55") (name "unconnected-(U15-BCBUS6-Pad58)") (class "Default")
      (node (ref "U15") (pin "58") (pinfunction "BCBUS6_58") (pintype "passive"))
    )
    (net (code "56") (name "unconnected-(U15-BDBUS2-Pad40)") (class "Default")
      (node (ref "U15") (pin "40") (pinfunction "BDBUS2_40") (pintype "passive"))
    )
    (net (code "57") (name "unconnected-(U15-BDBUS3-Pad41)") (class "Default")
      (node (ref "U15") (pin "41") (pinfunction "BDBUS3_41") (pintype "passive"))
    )
    (net (code "58") (name "unconnected-(U15-BDBUS4-Pad43)") (class "Default")
      (node (ref "U15") (pin "43") (pinfunction "BDBUS4_43") (pintype "passive"))
    )
    (net (code "59") (name "unconnected-(U15-BDBUS5-Pad44)") (class "Default")
      (node (ref "U15") (pin "44") (pinfunction "BDBUS5_44") (pintype "passive"))
    )
    (net (code "60") (name "unconnected-(U15-BDBUS6-Pad45)") (class "Default")
      (node (ref "U15") (pin "45") (pinfunction "BDBUS6_45") (pintype "passive"))
    )
    (net (code "61") (name "unconnected-(U15-BDBUS7-Pad46)") (class "Default")
      (node (ref "U15") (pin "46") (pinfunction "BDBUS7_46") (pintype "passive"))
    )
    (net (code "62") (name "unconnected-(U16-NC-Pad4)") (class "Default")
      (node (ref "U16") (pin "4") (pinfunction "NC_4") (pintype "passive+no_connect"))
    )
  )
)
